# main.net
KiCad netlist of a schematic drawn in Altium Designer
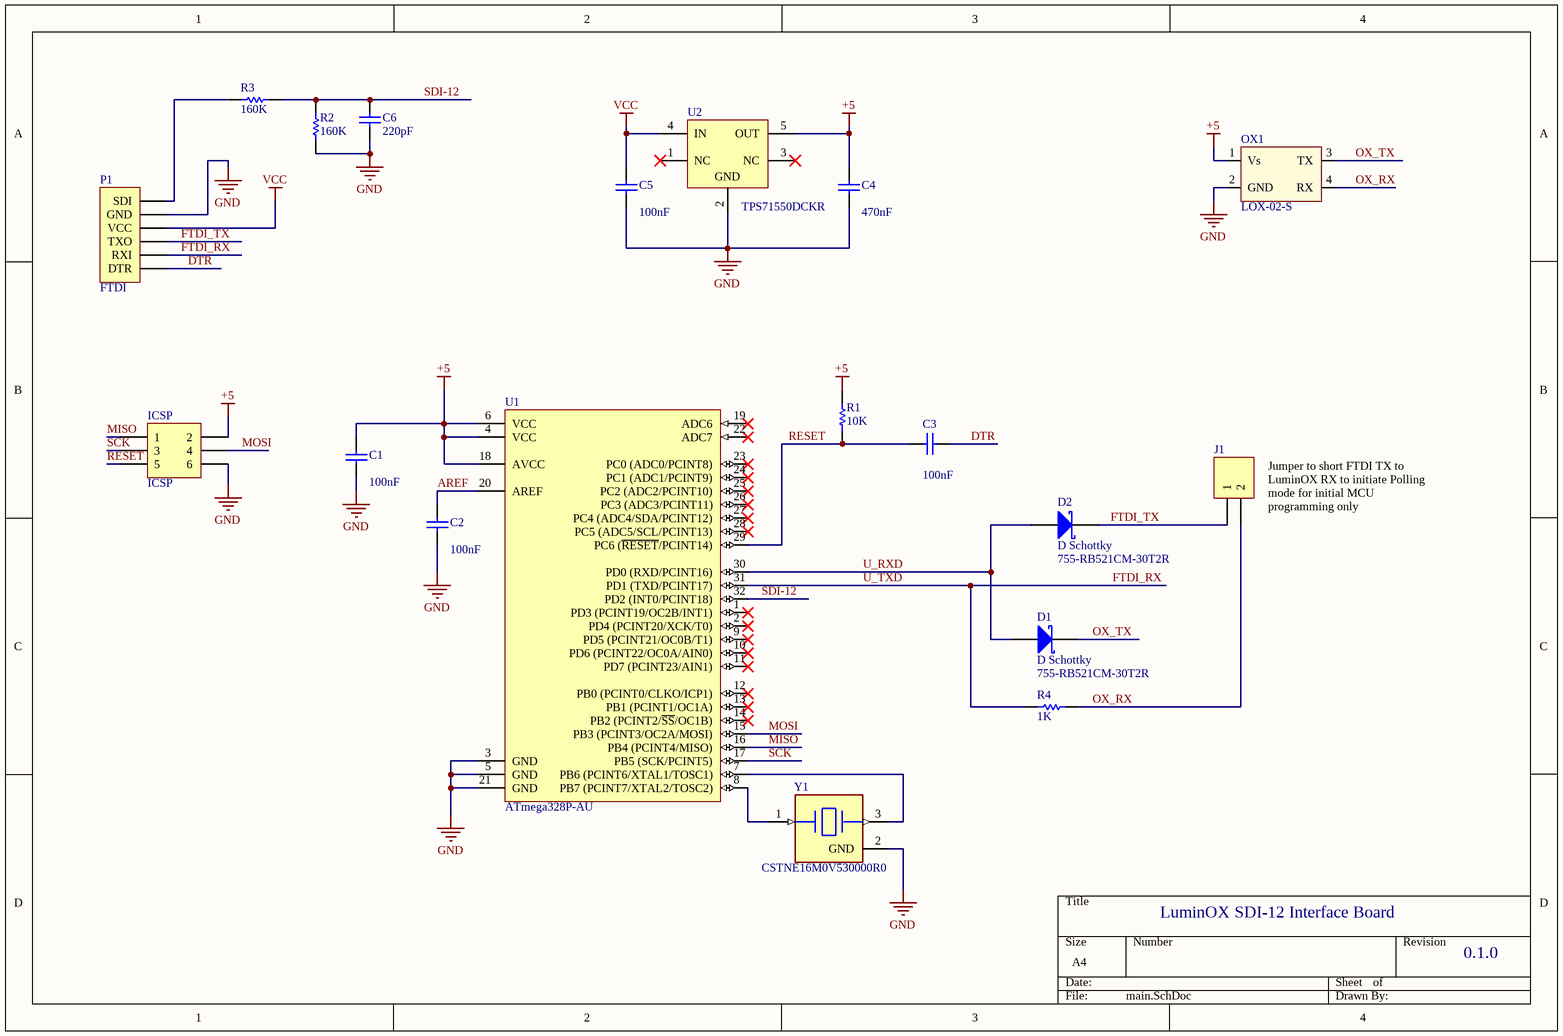
[diagram p0: main.SchDoc]

(export (version "E")
  (design (tool "Eeschema 10.0.6"))
  (components
    (comp (ref "C1")
      (value "100nF")
      (footprint "C0402_CAPC1005X06N")
      (description "Capacitor (Semiconductor SIM Model)")
      (fields (field (name "PUBLISHER") "Altium Limited"))
      (libsource (lib "Miscellaneous Devices") (part "Cap Semi"))
    )
    (comp (ref "C2")
      (value "100nF")
      (footprint "C0402_CAPC1005X06N")
      (description "Capacitor (Semiconductor SIM Model)")
      (fields (field (name "PUBLISHER") "Altium Limited"))
      (libsource (lib "Miscellaneous Devices") (part "Cap Semi"))
    )
    (comp (ref "C3")
      (value "100nF")
      (footprint "C0402_CAPC1005X06N")
      (description "Capacitor (Semiconductor SIM Model)")
      (fields (field (name "PUBLISHER") "Altium Limited"))
      (libsource (lib "Miscellaneous Devices") (part "Cap Semi"))
    )
    (comp (ref "C4")
      (value "470nF")
      (footprint "C0402_CAPC1005X06N")
      (description "Capacitor (Semiconductor SIM Model)")
      (fields (field (name "PUBLISHER") "Altium Limited"))
      (libsource (lib "Miscellaneous Devices") (part "Cap Semi"))
    )
    (comp (ref "C5")
      (value "100nF")
      (footprint "C0402_CAPC1005X06N")
      (description "Capacitor (Semiconductor SIM Model)")
      (fields (field (name "PUBLISHER") "Altium Limited"))
      (libsource (lib "Miscellaneous Devices") (part "Cap Semi"))
    )
    (comp (ref "C6")
      (value "220pF")
      (footprint "C0402_CAPC1005X06N")
      (description "Capacitor (Semiconductor SIM Model)")
      (fields (field (name "PUBLISHER") "Altium Limited"))
      (libsource (lib "Miscellaneous Devices") (part "Cap Semi"))
    )
    (comp (ref "D1")
      (value "D Schottky")
      (footprint "SOD923_SODFL98X40-2N")
      (description "DIODESCHOTTKY30V100MAVMN2M")
      (fields
        (field (name "SUPPLIER PART NUMBER 1") "755-RB521CM-30T2R")
        (field (name "MANUFACTURER") "Rohm")
        (field (name "MANUFACTURER PART NUMBER") "RB521CM-30T2R")
        (field (name "PUBLISHER") "Altium Limited")
      )
      (libsource (lib "Miscellaneous Devices") (part "D Schottky"))
    )
    (comp (ref "D2")
      (value "D Schottky")
      (footprint "SOD923_SODFL98X40-2N")
      (description "DIODESCHOTTKY30V100MAVMN2M")
      (fields
        (field (name "SUPPLIER PART NUMBER 1") "755-RB521CM-30T2R")
        (field (name "MANUFACTURER") "Rohm")
        (field (name "MANUFACTURER PART NUMBER") "RB521CM-30T2R")
        (field (name "PUBLISHER") "Altium Limited")
      )
      (libsource (lib "Miscellaneous Devices") (part "D Schottky"))
    )
    (comp (ref "ICSP")
      (value "ICSP")
      (footprint "HDR2X3")
      (description "Header, 3-Pin, Dual row")
      (fields (field (name "PUBLISHER") "Altium Limited"))
      (libsource (lib "Miscellaneous Connectors") (part "Header 3X2"))
    )
    (comp (ref "J1")
      (value "~")
      (footprint "HDR1X2")
      (description "Jumper to short FTDI TX to LuminOX RX to initiate Polling mode for initial MCU programming")
      (fields (field (name "PUBLISHER") "Altium Limited"))
      (libsource (lib "Miscellaneous Connectors") (part "Header 2"))
    )
    (comp (ref "OX1")
      (value "LOX-02-S")
      (footprint "LOX-02-S")
      (fields (field (name "MANUFACTURER") "SST Sensing"))
      (libsource (lib "hardware-luminox_to_sdi12_interface") (part "LOX-02-S"))
    )
    (comp (ref "P1")
      (value "FTDI")
      (footprint "HDR1X6")
      (description "Header, 6-Pin")
      (fields (field (name "PUBLISHER") "Altium Limited"))
      (libsource (lib "Miscellaneous Connectors") (part "Header 6"))
    )
    (comp (ref "R1")
      (value "10K")
      (footprint "R0402-RESC1005X04N")
      (description "Semiconductor Resistor")
      (fields (field (name "PUBLISHER") "Altium Limited"))
      (libsource (lib "Miscellaneous Devices") (part "Res Semi"))
    )
    (comp (ref "R2")
      (value "160K")
      (footprint "R0402-RESC1005X04N")
      (description "Semiconductor Resistor")
      (fields (field (name "PUBLISHER") "Altium Limited"))
      (libsource (lib "Miscellaneous Devices") (part "Res Semi"))
    )
    (comp (ref "R3")
      (value "160K")
      (footprint "R0402-RESC1005X04N")
      (description "Semiconductor Resistor")
      (fields (field (name "PUBLISHER") "Altium Limited"))
      (libsource (lib "Miscellaneous Devices") (part "Res Semi"))
    )
    (comp (ref "R4")
      (value "1K")
      (footprint "R0402-RESC1005X04N")
      (description "Semiconductor Resistor")
      (fields (field (name "PUBLISHER") "Altium Limited"))
      (libsource (lib "Miscellaneous Devices") (part "Res Semi"))
    )
    (comp (ref "U1")
      (value "ATmega328P-AU")
      (footprint "32A_M")
      (libsource (lib "Altium Content Vault") (part "MC-8B-ATM48-SQ32"))
    )
    (comp (ref "U2")
      (value "TPS71550DCKR")
      (footprint "DCK0005A_N")
      (fields (field (name "MANUFACTURER") "Texas Instruments"))
      (libsource (lib "Altium Content Vault") (part "TI-TPS71XXXX-XXDCK5"))
    )
    (comp (ref "Y1")
      (value "CSTNE16M0V530000R0")
      (footprint "FP-CSTNE16M0V530000R0-MFG")
      (description "CERAMIC RES 16.0000MHZ 15PF SMD")
      (fields (field (name "TOLERANCE") "0.5%") (field (name "MANUFACTURER") "Murata"))
      (libsource (lib "Altium Content Vault") (part "f88508b02107a2c8e6f46217c19d2b8"))
    )
  )
  (nets
    (net (code "1") (name "+5") (class "Default")
      (node (ref "C1") (pin "2") (pinfunction "2_2") (pintype "passive"))
      (node (ref "C4") (pin "2") (pinfunction "2_2") (pintype "passive"))
      (node (ref "ICSP") (pin "2") (pinfunction "2_2") (pintype "passive"))
      (node (ref "OX1") (pin "1") (pinfunction "Vs_1") (pintype "passive"))
      (node (ref "R1") (pin "2") (pinfunction "2_2") (pintype "passive"))
      (node (ref "U1") (pin "18") (pinfunction "AVCC_18") (pintype "power_in"))
      (node (ref "U1") (pin "4") (pinfunction "VCC_4") (pintype "power_in"))
      (node (ref "U1") (pin "6") (pinfunction "VCC_6") (pintype "power_in"))
      (node (ref "U2") (pin "5") (pinfunction "OUT_5") (pintype "power_in"))
    )
    (net (code "2") (name "/AREF") (class "Default")
      (node (ref "C2") (pin "2") (pinfunction "2_2") (pintype "passive"))
      (node (ref "U1") (pin "20") (pinfunction "AREF_20") (pintype "passive"))
    )
    (net (code "3") (name "/DTR") (class "Default")
      (node (ref "C3") (pin "1") (pinfunction "1_1") (pintype "passive"))
      (node (ref "P1") (pin "6") (pinfunction "DTR_6") (pintype "passive"))
    )
    (net (code "4") (name "/FTDI_RX") (class "Default")
      (node (ref "P1") (pin "5") (pinfunction "RXI_5") (pintype "passive"))
      (node (ref "R4") (pin "1") (pinfunction "1_1") (pintype "passive"))
      (node (ref "U1") (pin "31") (pinfunction "PD1_(TXD/PCINT17)_31") (pintype "bidirectional"))
    )
    (net (code "5") (name "/FTDI_TX") (class "Default")
      (node (ref "D2") (pin "2") (pinfunction "K_2") (pintype "passive"))
      (node (ref "J1") (pin "1") (pinfunction "1_1") (pintype "passive"))
      (node (ref "P1") (pin "4") (pinfunction "TXO_4") (pintype "passive"))
    )
    (net (code "6") (name "/MISO") (class "Default")
      (node (ref "ICSP") (pin "1") (pinfunction "1_1") (pintype "passive"))
      (node (ref "U1") (pin "16") (pinfunction "PB4_(PCINT4/MISO)_16") (pintype "bidirectional"))
    )
    (net (code "7") (name "/MOSI") (class "Default")
      (node (ref "ICSP") (pin "4") (pinfunction "4_4") (pintype "passive"))
      (node (ref "U1") (pin "15") (pinfunction "PB3_(PCINT3/OC2A/MOSI)_15") (pintype "bidirectional"))
    )
    (net (code "8") (name "/OX_RX") (class "Default")
      (node (ref "J1") (pin "2") (pinfunction "2_2") (pintype "passive"))
      (node (ref "OX1") (pin "4") (pinfunction "RX_4") (pintype "passive"))
      (node (ref "R4") (pin "2") (pinfunction "2_2") (pintype "passive"))
    )
    (net (code "9") (name "/OX_TX") (class "Default")
      (node (ref "D1") (pin "2") (pinfunction "K_2") (pintype "passive"))
      (node (ref "OX1") (pin "3") (pinfunction "TX_3") (pintype "passive"))
    )
    (net (code "10") (name "/RESET") (class "Default")
      (node (ref "C3") (pin "2") (pinfunction "2_2") (pintype "passive"))
      (node (ref "ICSP") (pin "5") (pinfunction "5_5") (pintype "passive"))
      (node (ref "R1") (pin "1") (pinfunction "1_1") (pintype "passive"))
      (node (ref "U1") (pin "29") (pinfunction "PC6_(~{RESET}/PCINT14)_29") (pintype "bidirectional"))
    )
    (net (code "11") (name "/SCK") (class "Default")
      (node (ref "ICSP") (pin "3") (pinfunction "3_3") (pintype "passive"))
      (node (ref "U1") (pin "17") (pinfunction "PB5_(SCK/PCINT5)_17") (pintype "bidirectional"))
    )
    (net (code "12") (name "/SDI-12") (class "Default")
      (node (ref "C6") (pin "1") (pinfunction "1_1") (pintype "passive"))
      (node (ref "R2") (pin "2") (pinfunction "2_2") (pintype "passive"))
      (node (ref "R3") (pin "1") (pinfunction "1_1") (pintype "passive"))
      (node (ref "U1") (pin "32") (pinfunction "PD2_(INT0/PCINT18)_32") (pintype "bidirectional"))
    )
    (net (code "13") (name "/U_RXD") (class "Default")
      (node (ref "D1") (pin "1") (pinfunction "A_1") (pintype "passive"))
      (node (ref "D2") (pin "1") (pinfunction "A_1") (pintype "passive"))
      (node (ref "U1") (pin "30") (pinfunction "PD0_(RXD/PCINT16)_30") (pintype "bidirectional"))
    )
    (net (code "14") (name "GND") (class "Default")
      (node (ref "C1") (pin "1") (pinfunction "1_1") (pintype "passive"))
      (node (ref "C2") (pin "1") (pinfunction "1_1") (pintype "passive"))
      (node (ref "C4") (pin "1") (pinfunction "1_1") (pintype "passive"))
      (node (ref "C5") (pin "1") (pinfunction "1_1") (pintype "passive"))
      (node (ref "C6") (pin "2") (pinfunction "2_2") (pintype "passive"))
      (node (ref "ICSP") (pin "6") (pinfunction "6_6") (pintype "passive"))
      (node (ref "OX1") (pin "2") (pinfunction "GND_2") (pintype "passive"))
      (node (ref "P1") (pin "2") (pinfunction "GND_2") (pintype "passive"))
      (node (ref "R2") (pin "1") (pinfunction "1_1") (pintype "passive"))
      (node (ref "U1") (pin "21") (pinfunction "GND_21") (pintype "power_in"))
      (node (ref "U1") (pin "3") (pinfunction "GND_3") (pintype "power_in"))
      (node (ref "U1") (pin "5") (pinfunction "GND_5") (pintype "power_in"))
      (node (ref "U2") (pin "2") (pinfunction "GND_2") (pintype "power_in"))
      (node (ref "Y1") (pin "2") (pinfunction "GND_2") (pintype "power_in"))
    )
    (net (code "15") (name "Net-(P1-SDI)") (class "Default")
      (node (ref "P1") (pin "1") (pinfunction "SDI_1") (pintype "passive"))
      (node (ref "R3") (pin "2") (pinfunction "2_2") (pintype "passive"))
    )
    (net (code "16") (name "Net-(U1-PB6_(PCINT6{slash}XTAL1{slash}TOSC1))") (class "Default")
      (node (ref "U1") (pin "7") (pinfunction "PB6_(PCINT6/XTAL1/TOSC1)_7") (pintype "bidirectional"))
      (node (ref "Y1") (pin "3") (pinfunction "Output_3") (pintype "output"))
    )
    (net (code "17") (name "Net-(U1-PB7_(PCINT7{slash}XTAL2{slash}TOSC2))") (class "Default")
      (node (ref "U1") (pin "8") (pinfunction "PB7_(PCINT7/XTAL2/TOSC2)_8") (pintype "bidirectional"))
      (node (ref "Y1") (pin "1") (pinfunction "Input_1") (pintype "input"))
    )
    (net (code "18") (name "VCC") (class "Default")
      (node (ref "C5") (pin "2") (pinfunction "2_2") (pintype "passive"))
      (node (ref "P1") (pin "3") (pinfunction "VCC_3") (pintype "passive"))
      (node (ref "U2") (pin "4") (pinfunction "IN_4") (pintype "power_in"))
    )
    (net (code "19") (name "unconnected-(U1-ADC6-Pad19)") (class "Default")
      (node (ref "U1") (pin "19") (pinfunction "ADC6_19") (pintype "input+no_connect"))
    )
    (net (code "20") (name "unconnected-(U1-ADC7-Pad22)") (class "Default")
      (node (ref "U1") (pin "22") (pinfunction "ADC7_22") (pintype "input+no_connect"))
    )
    (net (code "21") (name "unconnected-(U1-PB0_(PCINT0{slash}CLKO{slash}ICP1)-Pad12)") (class "Default")
      (node (ref "U1") (pin "12") (pinfunction "PB0_(PCINT0/CLKO/ICP1)_12") (pintype "bidirectional+no_connect"))
    )
    (net (code "22") (name "unconnected-(U1-PB1_(PCINT1{slash}OC1A)-Pad13)") (class "Default")
      (node (ref "U1") (pin "13") (pinfunction "PB1_(PCINT1/OC1A)_13") (pintype "bidirectional+no_connect"))
    )
    (net (code "23") (name "unconnected-(U1-PB2_(PCINT2{slash}~{SS}{slash}OC1B)-Pad14)") (class "Default")
      (node (ref "U1") (pin "14") (pinfunction "PB2_(PCINT2/~{SS}/OC1B)_14") (pintype "bidirectional+no_connect"))
    )
    (net (code "24") (name "unconnected-(U1-PC0_(ADC0{slash}PCINT8)-Pad23)") (class "Default")
      (node (ref "U1") (pin "23") (pinfunction "PC0_(ADC0/PCINT8)_23") (pintype "bidirectional+no_connect"))
    )
    (net (code "25") (name "unconnected-(U1-PC1_(ADC1{slash}PCINT9)-Pad24)") (class "Default")
      (node (ref "U1") (pin "24") (pinfunction "PC1_(ADC1/PCINT9)_24") (pintype "bidirectional+no_connect"))
    )
    (net (code "26") (name "unconnected-(U1-PC2_(ADC2{slash}PCINT10)-Pad25)") (class "Default")
      (node (ref "U1") (pin "25") (pinfunction "PC2_(ADC2/PCINT10)_25") (pintype "bidirectional+no_connect"))
    )
    (net (code "27") (name "unconnected-(U1-PC3_(ADC3{slash}PCINT11)-Pad26)") (class "Default")
      (node (ref "U1") (pin "26") (pinfunction "PC3_(ADC3/PCINT11)_26") (pintype "bidirectional+no_connect"))
    )
    (net (code "28") (name "unconnected-(U1-PC4_(ADC4{slash}SDA{slash}PCINT12)-Pad27)") (class "Default")
      (node (ref "U1") (pin "27") (pinfunction "PC4_(ADC4/SDA/PCINT12)_27") (pintype "bidirectional+no_connect"))
    )
    (net (code "29") (name "unconnected-(U1-PC5_(ADC5{slash}SCL{slash}PCINT13)-Pad28)") (class "Default")
      (node (ref "U1") (pin "28") (pinfunction "PC5_(ADC5/SCL/PCINT13)_28") (pintype "bidirectional+no_connect"))
    )
    (net (code "30") (name "unconnected-(U1-PD3_(PCINT19{slash}OC2B{slash}INT1)-Pad1)") (class "Default")
      (node (ref "U1") (pin "1") (pinfunction "PD3_(PCINT19/OC2B/INT1)_1") (pintype "bidirectional+no_connect"))
    )
    (net (code "31") (name "unconnected-(U1-PD4_(PCINT20{slash}XCK{slash}T0)-Pad2)") (class "Default")
      (node (ref "U1") (pin "2") (pinfunction "PD4_(PCINT20/XCK/T0)_2") (pintype "bidirectional+no_connect"))
    )
    (net (code "32") (name "unconnected-(U1-PD5_(PCINT21{slash}OC0B{slash}T1)-Pad9)") (class "Default")
      (node (ref "U1") (pin "9") (pinfunction "PD5_(PCINT21/OC0B/T1)_9") (pintype "bidirectional+no_connect"))
    )
    (net (code "33") (name "unconnected-(U1-PD6_(PCINT22{slash}OC0A{slash}AIN0)-Pad10)") (class "Default")
      (node (ref "U1") (pin "10") (pinfunction "PD6_(PCINT22/OC0A/AIN0)_10") (pintype "bidirectional+no_connect"))
    )
    (net (code "34") (name "unconnected-(U1-PD7_(PCINT23{slash}AIN1)-Pad11)") (class "Default")
      (node (ref "U1") (pin "11") (pinfunction "PD7_(PCINT23/AIN1)_11") (pintype "bidirectional+no_connect"))
    )
    (net (code "35") (name "unconnected-(U2-NC-Pad1)") (class "Default")
      (node (ref "U2") (pin "1") (pinfunction "NC_1") (pintype "passive+no_connect"))
    )
    (net (code "36") (name "unconnected-(U2-NC-Pad3)") (class "Default")
      (node (ref "U2") (pin "3") (pinfunction "NC_3") (pintype "passive+no_connect"))
    )
  )
)
